# sensor.net
KiCad netlist of a schematic drawn in EAGLE
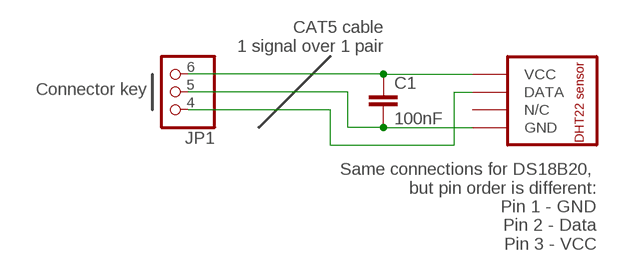
[diagram p0: schematic, sheet 1]

(export (version "E")
  (design (tool "Eeschema 10.0.6"))
  (components
    (comp (ref "C1")
      (value "100nF")
      (footprint "eagle-import:C025-024X044")
      (libsource (lib "eagle-import") (part "C-EU025-024X044"))
    )
    (comp (ref "JP1")
      (value "PINHD-1X3MOLEX")
      (footprint "eagle-import:1X3_MOLEX")
      (libsource (lib "eagle-import") (part "PINHD-1X3MOLEX"))
    )
    (comp (ref "U$1")
      (value "DHT22")
      (footprint "eagle-import:DHT22")
      (libsource (lib "eagle-import") (part "DHT22"))
    )
  )
  (nets
    (net (code "1") (name "Net-(JP1-1)") (class "Default")
      (node (ref "JP1") (pin "4") (pinfunction "1_4") (pintype "passive"))
      (node (ref "U$1") (pin "P$2") (pinfunction "DATA_P$2") (pintype "bidirectional"))
    )
    (net (code "2") (name "Net-(JP1-2)") (class "Default")
      (node (ref "C1") (pin "2") (pinfunction "2_2") (pintype "passive"))
      (node (ref "JP1") (pin "5") (pinfunction "2_5") (pintype "passive"))
      (node (ref "U$1") (pin "P$4") (pinfunction "GND_P$4") (pintype "bidirectional"))
    )
    (net (code "3") (name "Net-(JP1-3)") (class "Default")
      (node (ref "C1") (pin "1") (pinfunction "1_1") (pintype "passive"))
      (node (ref "JP1") (pin "6") (pinfunction "3_6") (pintype "passive"))
      (node (ref "U$1") (pin "P$1") (pinfunction "VCC_P$1") (pintype "bidirectional"))
    )
    (net (code "4") (name "unconnected-(U$1-N{slash}C-PadP$3)") (class "Default")
      (node (ref "U$1") (pin "P$3") (pinfunction "N/C_P$3") (pintype "bidirectional"))
    )
  )
)
